# opaq_n1.net
KiCad netlist of a schematic drawn in EAGLE
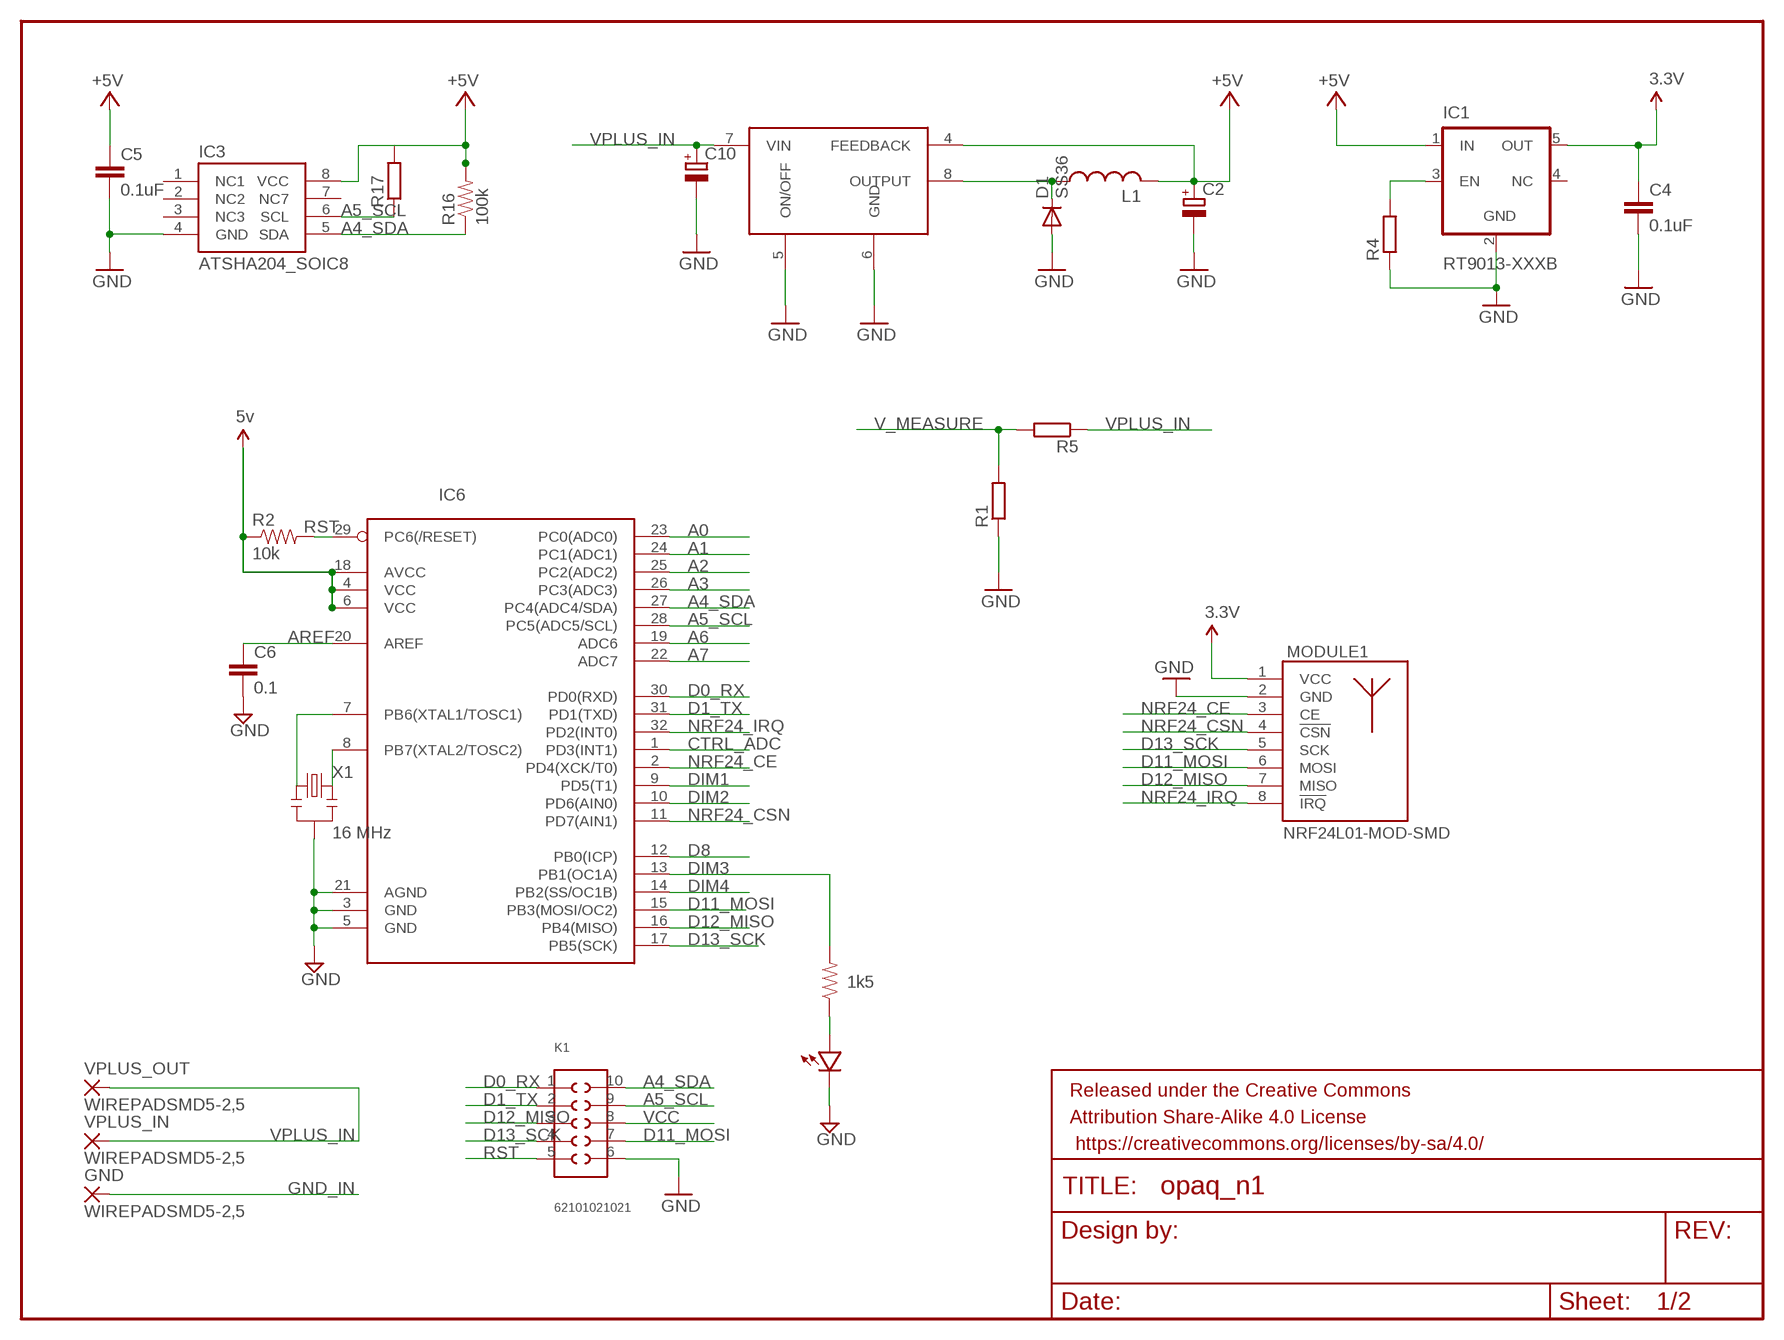
[diagram p0: schematic, sheet 1]
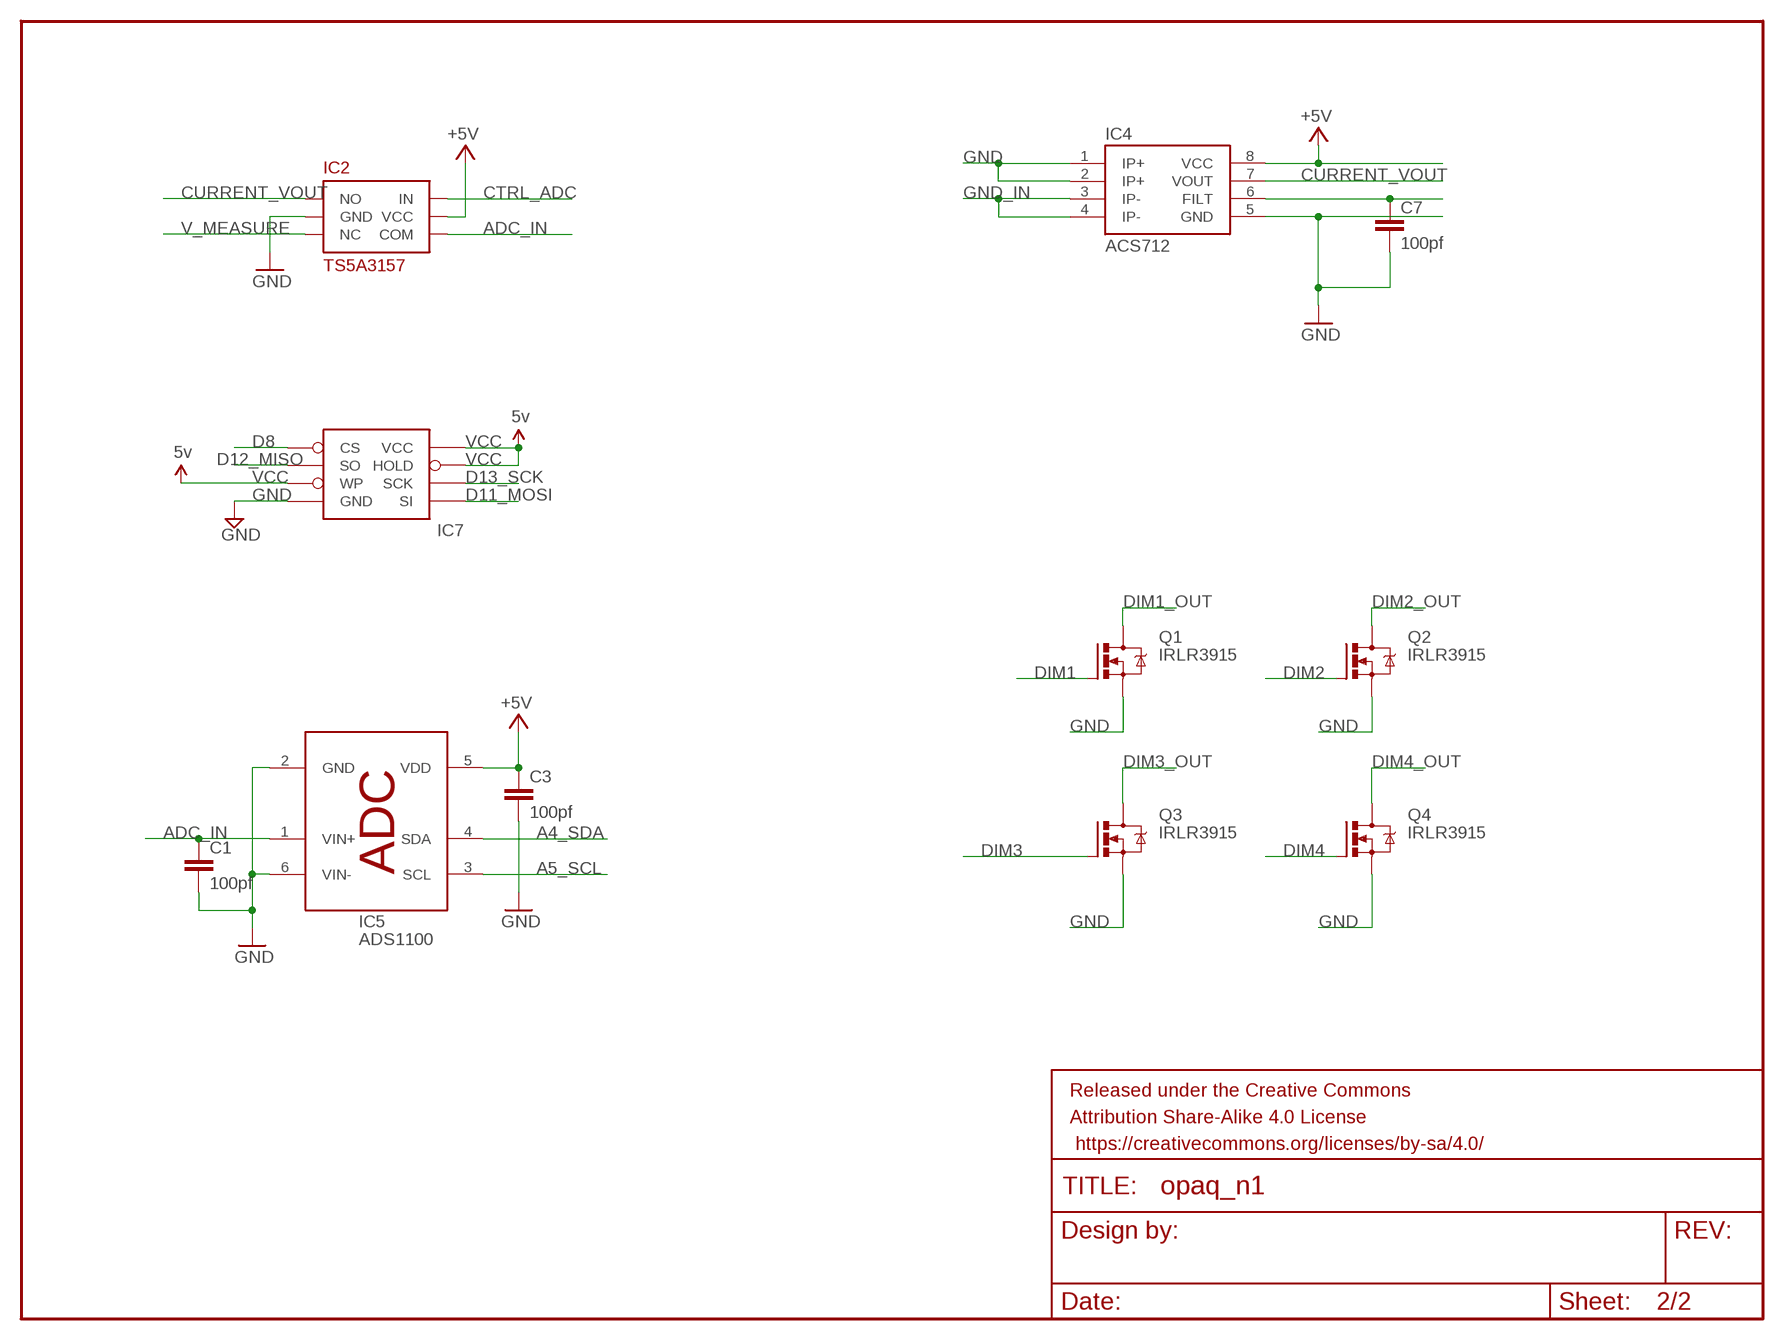
[diagram p1: schematic, sheet 2]

(export (version "E")
  (design (tool "Eeschema 10.0.6"))
  (components
    (comp (ref "C1")
      (value "100pf")
      (footprint "eagle-import:0402-CAP")
      (libsource (lib "eagle-import") (part "SparkFun-Passives_CAP0402-CAP"))
    )
    (comp (ref "C3")
      (value "100pf")
      (footprint "eagle-import:0402-CAP")
      (libsource (lib "eagle-import") (part "SparkFun-Passives_CAP0402-CAP"))
    )
    (comp (ref "C7")
      (value "100pf")
      (footprint "eagle-import:0402-CAP")
      (libsource (lib "eagle-import") (part "SparkFun-Passives_CAP0402-CAP"))
    )
    (comp (ref "FRAME2")
      (value "FRAME-LETTERNO_PACKAGE")
      (footprint "eagle-import:DUMMY")
      (fields (field (name "DESIGNER") "Nobody"))
      (libsource (lib "eagle-import") (part "FRAME-LETTERNO_PACKAGE"))
    )
    (comp (ref "IC2")
      (value "TS5A3157")
      (footprint "eagle-import:SOT23-6")
      (libsource (lib "eagle-import") (part "TS5A3157"))
    )
    (comp (ref "IC4")
      (value "ACS712")
      (footprint "eagle-import:SO08")
      (libsource (lib "eagle-import") (part "ACS712"))
    )
    (comp (ref "IC5")
      (value "ADS1100")
      (footprint "eagle-import:SOT23-6")
      (fields (field (name "MF") "TI"))
      (libsource (lib "eagle-import") (part "ADS1100"))
    )
    (comp (ref "IC7")
      (value "AT25F512BWIDE_5.3MM")
      (footprint "eagle-import:SO08WIDE")
      (libsource (lib "eagle-import") (part "AT25F512BWIDE_5.3MM"))
    )
    (comp (ref "Q1")
      (value "IRLR3915")
      (footprint "eagle-import:D-PAK_TO252AA")
      (libsource (lib "eagle-import") (part "IRLR3915"))
    )
    (comp (ref "Q2")
      (value "IRLR3915")
      (footprint "eagle-import:D-PAK_TO252AA")
      (libsource (lib "eagle-import") (part "IRLR3915"))
    )
    (comp (ref "Q3")
      (value "IRLR3915")
      (footprint "eagle-import:D-PAK_TO252AA")
      (libsource (lib "eagle-import") (part "IRLR3915"))
    )
    (comp (ref "Q4")
      (value "IRLR3915")
      (footprint "eagle-import:D-PAK_TO252AA")
      (libsource (lib "eagle-import") (part "IRLR3915"))
    )
    (comp (ref "C2")
      (value "CPOL-EUC/6032-28R")
      (footprint "eagle-import:C_6032-28R")
      (libsource (lib "eagle-import") (part "CPOL-EUC/6032-28R"))
    )
    (comp (ref "C4")
      (value "0.1uF")
      (footprint "eagle-import:0805")
      (libsource (lib "eagle-import") (part "SparkFun-Passives_CAP0805"))
    )
    (comp (ref "C5")
      (value "0.1uF")
      (footprint "eagle-import:0805")
      (libsource (lib "eagle-import") (part "SparkFun-Passives_CAP0805"))
    )
    (comp (ref "C6")
      (value "0.1")
      (footprint "eagle-import:0603-CAP")
      (libsource (lib "eagle-import") (part "CAP0603-CAP"))
    )
    (comp (ref "C10")
      (value "CPOL-EUD/7343-31R")
      (footprint "eagle-import:D_7343-31R")
      (libsource (lib "eagle-import") (part "CPOL-EUD/7343-31R"))
    )
    (comp (ref "D1")
      (value "SS36")
      (footprint "eagle-import:SMA-DIODE")
      (libsource (lib "eagle-import") (part "DIODESMA"))
    )
    (comp (ref "DIM")
      (value "LED0603")
      (footprint "eagle-import:0603-LED")
      (libsource (lib "eagle-import") (part "LED0603"))
    )
    (comp (ref "FRAME1")
      (value "FRAME-LETTER")
      (footprint "eagle-import:CREATIVE_COMMONS")
      (libsource (lib "eagle-import") (part "FRAME-LETTER"))
    )
    (comp (ref "GND")
      (value "WIREPADSMD5-2,5")
      (footprint "eagle-import:5-2,5")
      (libsource (lib "eagle-import") (part "WIREPADSMD5-2,5"))
    )
    (comp (ref "IC1")
      (value "RT9013-XXXB")
      (footprint "eagle-import:SOT23-5")
      (libsource (lib "eagle-import") (part "RT9013-XXXB"))
    )
    (comp (ref "IC3")
      (value "ATSHA204_SOIC8")
      (footprint "eagle-import:SOIC8")
      (libsource (lib "eagle-import") (part "ATSHA204_SOIC8"))
    )
    (comp (ref "IC6")
      (value "ATMega-328")
      (footprint "eagle-import:MLF32")
      (libsource (lib "eagle-import") (part "ATMEGA168/328MLF"))
    )
    (comp (ref "IC8")
      (value "LM2594HV")
      (footprint "eagle-import:SO08")
      (libsource (lib "eagle-import") (part "LM2594"))
    )
    (comp (ref "K1")
      (value "62101021021")
      (footprint "eagle-import:62101021021")
      (libsource (lib "eagle-import") (part "62101021021"))
    )
    (comp (ref "L1")
      (value "NR6045")
      (footprint "eagle-import:2525")
      (libsource (lib "eagle-import") (part "NR6045"))
    )
    (comp (ref "MODULE1")
      (value "NRF24L01-MOD-SMD")
      (footprint "eagle-import:SMD8-MODULE")
      (libsource (lib "eagle-import") (part "NRF24L01-MOD-SMD"))
    )
    (comp (ref "R1")
      (value "R-EU_R0805")
      (footprint "eagle-import:0805")
      (libsource (lib "eagle-import") (part "R-EU_R0805"))
    )
    (comp (ref "R2")
      (value "10k")
      (footprint "eagle-import:0603-RES")
      (libsource (lib "eagle-import") (part "RESISTOR0603-RES"))
    )
    (comp (ref "R3")
      (value "1k5")
      (footprint "eagle-import:0603-RES")
      (libsource (lib "eagle-import") (part "RESISTOR0603-RES"))
    )
    (comp (ref "R4")
      (value "R-EU_R0805")
      (footprint "eagle-import:0805")
      (libsource (lib "eagle-import") (part "R-EU_R0805"))
    )
    (comp (ref "R5")
      (value "R-EU_R0805")
      (footprint "eagle-import:0805")
      (libsource (lib "eagle-import") (part "R-EU_R0805"))
    )
    (comp (ref "R16")
      (value "100k")
      (footprint "eagle-import:0805")
      (libsource (lib "eagle-import") (part "SparkFun-Passives_RESISTOR0805-RES"))
    )
    (comp (ref "R17")
      (value "R-EU_R0805")
      (footprint "eagle-import:0805")
      (libsource (lib "eagle-import") (part "R-EU_R0805"))
    )
    (comp (ref "VPLUS_IN")
      (value "WIREPADSMD5-2,5")
      (footprint "eagle-import:5-2,5")
      (libsource (lib "eagle-import") (part "WIREPADSMD5-2,5"))
    )
    (comp (ref "VPLUS_OUT")
      (value "WIREPADSMD5-2,5")
      (footprint "eagle-import:5-2,5")
      (libsource (lib "eagle-import") (part "WIREPADSMD5-2,5"))
    )
    (comp (ref "X1")
      (value "16 MHz")
      (footprint "eagle-import:RESONATOR-SMD")
      (libsource (lib "eagle-import") (part "RESONATORSMD"))
    )
  )
  (nets
    (net (code "1") (name "+5V") (class "Default")
      (node (ref "C2") (pin "+") (pinfunction "+_+") (pintype "passive"))
      (node (ref "C3") (pin "1") (pinfunction "1_1") (pintype "passive"))
      (node (ref "C5") (pin "1") (pinfunction "1_1") (pintype "passive"))
      (node (ref "IC1") (pin "1") (pinfunction "IN_1") (pintype "input"))
      (node (ref "IC2") (pin "5") (pinfunction "VCC_5") (pintype "bidirectional"))
      (node (ref "IC3") (pin "8") (pinfunction "VCC_8") (pintype "power_in"))
      (node (ref "IC4") (pin "8") (pinfunction "VCC_8") (pintype "bidirectional"))
      (node (ref "IC5") (pin "5") (pinfunction "VDD_5") (pintype "power_in"))
      (node (ref "IC8") (pin "4") (pinfunction "FEEDBACK_4") (pintype "bidirectional"))
      (node (ref "L1") (pin "P$1") (pinfunction "P$1_P$1") (pintype "passive"))
      (node (ref "R16") (pin "2") (pinfunction "2_2") (pintype "passive"))
      (node (ref "R17") (pin "2") (pinfunction "2_2") (pintype "passive"))
    )
    (net (code "2") (name "3.3V") (class "Default")
      (node (ref "C4") (pin "1") (pinfunction "1_1") (pintype "passive"))
      (node (ref "IC1") (pin "5") (pinfunction "OUT_5") (pintype "passive"))
      (node (ref "MODULE1") (pin "1") (pinfunction "VCC_1") (pintype "power_in"))
    )
    (net (code "3") (name "A0") (class "Default")
      (node (ref "IC6") (pin "23") (pinfunction "PC0(ADC0)_23") (pintype "bidirectional"))
    )
    (net (code "4") (name "A1") (class "Default")
      (node (ref "IC6") (pin "24") (pinfunction "PC1(ADC1)_24") (pintype "bidirectional"))
    )
    (net (code "5") (name "A2") (class "Default")
      (node (ref "IC6") (pin "25") (pinfunction "PC2(ADC2)_25") (pintype "bidirectional"))
    )
    (net (code "6") (name "A3") (class "Default")
      (node (ref "IC6") (pin "26") (pinfunction "PC3(ADC3)_26") (pintype "bidirectional"))
    )
    (net (code "7") (name "A4_SDA") (class "Default")
      (node (ref "IC3") (pin "5") (pinfunction "SDA_5") (pintype "bidirectional"))
      (node (ref "IC5") (pin "4") (pinfunction "SDA_4") (pintype "bidirectional"))
      (node (ref "IC6") (pin "27") (pinfunction "PC4(ADC4/SDA)_27") (pintype "bidirectional"))
      (node (ref "K1") (pin "10") (pinfunction "10_10") (pintype "passive"))
      (node (ref "R16") (pin "1") (pinfunction "1_1") (pintype "passive"))
    )
    (net (code "8") (name "A5_SCL") (class "Default")
      (node (ref "IC3") (pin "6") (pinfunction "SCL_6") (pintype "bidirectional"))
      (node (ref "IC5") (pin "3") (pinfunction "SCL_3") (pintype "input"))
      (node (ref "IC6") (pin "28") (pinfunction "PC5(ADC5/SCL)_28") (pintype "bidirectional"))
      (node (ref "K1") (pin "9") (pinfunction "9_9") (pintype "passive"))
      (node (ref "R17") (pin "1") (pinfunction "1_1") (pintype "passive"))
    )
    (net (code "9") (name "A6") (class "Default")
      (node (ref "IC6") (pin "19") (pinfunction "ADC6_19") (pintype "bidirectional"))
    )
    (net (code "10") (name "A7") (class "Default")
      (node (ref "IC6") (pin "22") (pinfunction "ADC7_22") (pintype "bidirectional"))
    )
    (net (code "11") (name "ADC_IN") (class "Default")
      (node (ref "C1") (pin "1") (pinfunction "1_1") (pintype "passive"))
      (node (ref "IC2") (pin "4") (pinfunction "COM_4") (pintype "bidirectional"))
      (node (ref "IC5") (pin "1") (pinfunction "VIN+_1") (pintype "input"))
    )
    (net (code "12") (name "AREF") (class "Default")
      (node (ref "C6") (pin "1") (pinfunction "1_1") (pintype "passive"))
      (node (ref "IC6") (pin "20") (pinfunction "AREF_20") (pintype "bidirectional"))
    )
    (net (code "13") (name "CTRL_ADC") (class "Default")
      (node (ref "IC2") (pin "6") (pinfunction "IN_6") (pintype "bidirectional"))
      (node (ref "IC6") (pin "1") (pinfunction "PD3(INT1)_1") (pintype "bidirectional"))
    )
    (net (code "14") (name "CURRENT_VOUT") (class "Default")
      (node (ref "IC2") (pin "1") (pinfunction "NO_1") (pintype "bidirectional"))
      (node (ref "IC4") (pin "7") (pinfunction "VOUT_7") (pintype "bidirectional"))
    )
    (net (code "15") (name "D0_RX") (class "Default")
      (node (ref "IC6") (pin "30") (pinfunction "PD0(RXD)_30") (pintype "bidirectional"))
      (node (ref "K1") (pin "1") (pinfunction "1_1") (pintype "passive"))
    )
    (net (code "16") (name "D1_TX") (class "Default")
      (node (ref "IC6") (pin "31") (pinfunction "PD1(TXD)_31") (pintype "bidirectional"))
      (node (ref "K1") (pin "2") (pinfunction "2_2") (pintype "passive"))
    )
    (net (code "17") (name "D8") (class "Default")
      (node (ref "IC6") (pin "12") (pinfunction "PB0(ICP)_12") (pintype "bidirectional"))
      (node (ref "IC7") (pin "1") (pinfunction "CS_1") (pintype "bidirectional"))
    )
    (net (code "18") (name "D11_MOSI") (class "Default")
      (node (ref "IC6") (pin "15") (pinfunction "PB3(MOSI/OC2)_15") (pintype "bidirectional"))
      (node (ref "IC7") (pin "5") (pinfunction "SI_5") (pintype "bidirectional"))
      (node (ref "K1") (pin "7") (pinfunction "7_7") (pintype "passive"))
      (node (ref "MODULE1") (pin "6") (pinfunction "MOSI_6") (pintype "input"))
    )
    (net (code "19") (name "D12_MISO") (class "Default")
      (node (ref "IC6") (pin "16") (pinfunction "PB4(MISO)_16") (pintype "bidirectional"))
      (node (ref "IC7") (pin "2") (pinfunction "SO_2") (pintype "bidirectional"))
      (node (ref "K1") (pin "3") (pinfunction "3_3") (pintype "passive"))
      (node (ref "MODULE1") (pin "7") (pinfunction "MISO_7") (pintype "output"))
    )
    (net (code "20") (name "D13_SCK") (class "Default")
      (node (ref "IC6") (pin "17") (pinfunction "PB5(SCK)_17") (pintype "bidirectional"))
      (node (ref "IC7") (pin "6") (pinfunction "SCK_6") (pintype "bidirectional"))
      (node (ref "K1") (pin "4") (pinfunction "4_4") (pintype "passive"))
      (node (ref "MODULE1") (pin "5") (pinfunction "SCK_5") (pintype "input"))
    )
    (net (code "21") (name "DIM1") (class "Default")
      (node (ref "IC6") (pin "9") (pinfunction "PD5(T1)_9") (pintype "bidirectional"))
      (node (ref "Q1") (pin "1") (pinfunction "G_1") (pintype "passive"))
    )
    (net (code "22") (name "DIM1_OUT") (class "Default")
      (node (ref "Q1") (pin "4") (pinfunction "D_4") (pintype "passive"))
    )
    (net (code "23") (name "DIM2") (class "Default")
      (node (ref "IC6") (pin "10") (pinfunction "PD6(AIN0)_10") (pintype "bidirectional"))
      (node (ref "Q2") (pin "1") (pinfunction "G_1") (pintype "passive"))
    )
    (net (code "24") (name "DIM2_OUT") (class "Default")
      (node (ref "Q2") (pin "4") (pinfunction "D_4") (pintype "passive"))
    )
    (net (code "25") (name "DIM3") (class "Default")
      (node (ref "IC6") (pin "13") (pinfunction "PB1(OC1A)_13") (pintype "bidirectional"))
      (node (ref "Q3") (pin "1") (pinfunction "G_1") (pintype "passive"))
      (node (ref "R3") (pin "2") (pinfunction "2_2") (pintype "passive"))
    )
    (net (code "26") (name "DIM3_OUT") (class "Default")
      (node (ref "Q3") (pin "4") (pinfunction "D_4") (pintype "passive"))
    )
    (net (code "27") (name "DIM4") (class "Default")
      (node (ref "IC6") (pin "14") (pinfunction "PB2(SS/OC1B)_14") (pintype "bidirectional"))
      (node (ref "Q4") (pin "1") (pinfunction "G_1") (pintype "passive"))
    )
    (net (code "28") (name "DIM4_OUT") (class "Default")
      (node (ref "Q4") (pin "4") (pinfunction "D_4") (pintype "passive"))
    )
    (net (code "29") (name "GND") (class "Default")
      (node (ref "C1") (pin "2") (pinfunction "2_2") (pintype "passive"))
      (node (ref "C10") (pin "-") (pinfunction "-_-") (pintype "passive"))
      (node (ref "C2") (pin "-") (pinfunction "-_-") (pintype "passive"))
      (node (ref "C3") (pin "2") (pinfunction "2_2") (pintype "passive"))
      (node (ref "C4") (pin "2") (pinfunction "2_2") (pintype "passive"))
      (node (ref "C5") (pin "2") (pinfunction "2_2") (pintype "passive"))
      (node (ref "C6") (pin "2") (pinfunction "2_2") (pintype "passive"))
      (node (ref "C7") (pin "2") (pinfunction "2_2") (pintype "passive"))
      (node (ref "D1") (pin "A") (pinfunction "A_A") (pintype "passive"))
      (node (ref "DIM") (pin "MINUS") (pinfunction "MINUS_MINUS") (pintype "passive"))
      (node (ref "IC1") (pin "2") (pinfunction "GND_2") (pintype "power_in"))
      (node (ref "IC2") (pin "2") (pinfunction "GND_2") (pintype "bidirectional"))
      (node (ref "IC3") (pin "4") (pinfunction "GND_4") (pintype "power_in"))
      (node (ref "IC4") (pin "1") (pinfunction "IP+_1") (pintype "bidirectional"))
      (node (ref "IC4") (pin "2") (pinfunction "IP+_2") (pintype "bidirectional"))
      (node (ref "IC4") (pin "5") (pinfunction "GND_5") (pintype "bidirectional"))
      (node (ref "IC5") (pin "2") (pinfunction "GND_2") (pintype "power_in"))
      (node (ref "IC5") (pin "6") (pinfunction "VIN-_6") (pintype "input"))
      (node (ref "IC6") (pin "21") (pinfunction "AGND_21") (pintype "bidirectional"))
      (node (ref "IC6") (pin "3") (pinfunction "GND_3") (pintype "bidirectional"))
      (node (ref "IC6") (pin "5") (pinfunction "GND_5") (pintype "bidirectional"))
      (node (ref "IC7") (pin "4") (pinfunction "GND_4") (pintype "bidirectional"))
      (node (ref "IC8") (pin "5") (pinfunction "ON/OFF_5") (pintype "bidirectional"))
      (node (ref "IC8") (pin "6") (pinfunction "GND_6") (pintype "bidirectional"))
      (node (ref "K1") (pin "6") (pinfunction "6_6") (pintype "passive"))
      (node (ref "MODULE1") (pin "2") (pinfunction "GND_2") (pintype "power_in"))
      (node (ref "Q1") (pin "3") (pinfunction "S_3") (pintype "passive"))
      (node (ref "Q2") (pin "3") (pinfunction "S_3") (pintype "passive"))
      (node (ref "Q3") (pin "3") (pinfunction "S_3") (pintype "passive"))
      (node (ref "Q4") (pin "3") (pinfunction "S_3") (pintype "passive"))
      (node (ref "R1") (pin "1") (pinfunction "1_1") (pintype "passive"))
      (node (ref "R4") (pin "1") (pinfunction "1_1") (pintype "passive"))
      (node (ref "X1") (pin "2") (pinfunction "2_2") (pintype "passive"))
    )
    (net (code "30") (name "GND_IN") (class "Default")
      (node (ref "GND") (pin "1") (pinfunction "P_1") (pintype "passive"))
      (node (ref "IC4") (pin "3") (pinfunction "IP-_3") (pintype "bidirectional"))
      (node (ref "IC4") (pin "4") (pinfunction "IP-_4") (pintype "bidirectional"))
    )
    (net (code "31") (name "NRF24_CE") (class "Default")
      (node (ref "IC6") (pin "2") (pinfunction "PD4(XCK/T0)_2") (pintype "bidirectional"))
      (node (ref "MODULE1") (pin "3") (pinfunction "CE_3") (pintype "input"))
    )
    (net (code "32") (name "NRF24_CSN") (class "Default")
      (node (ref "IC6") (pin "11") (pinfunction "PD7(AIN1)_11") (pintype "bidirectional"))
      (node (ref "MODULE1") (pin "4") (pinfunction "~{CSN}_4") (pintype "input"))
    )
    (net (code "33") (name "NRF24_IRQ") (class "Default")
      (node (ref "IC6") (pin "32") (pinfunction "PD2(INT0)_32") (pintype "bidirectional"))
      (node (ref "MODULE1") (pin "8") (pinfunction "~{IRQ}_8") (pintype "open_collector"))
    )
    (net (code "34") (name "Net-(DIM-PadPLUS)") (class "Default")
      (node (ref "DIM") (pin "PLUS") (pinfunction "PLUS_PLUS") (pintype "passive"))
      (node (ref "R3") (pin "1") (pinfunction "1_1") (pintype "passive"))
    )
    (net (code "35") (name "Net-(IC1-EN)") (class "Default")
      (node (ref "IC1") (pin "3") (pinfunction "EN_3") (pintype "input"))
      (node (ref "R4") (pin "2") (pinfunction "2_2") (pintype "passive"))
    )
    (net (code "36") (name "Net-(IC4-FILT)") (class "Default")
      (node (ref "C7") (pin "1") (pinfunction "1_1") (pintype "passive"))
      (node (ref "IC4") (pin "6") (pinfunction "FILT_6") (pintype "bidirectional"))
    )
    (net (code "37") (name "Net-(IC6-PB6(XTAL1{slash}TOSC1))") (class "Default")
      (node (ref "IC6") (pin "7") (pinfunction "PB6(XTAL1/TOSC1)_7") (pintype "bidirectional"))
      (node (ref "X1") (pin "1") (pinfunction "1_1") (pintype "passive"))
    )
    (net (code "38") (name "Net-(IC6-PB7(XTAL2{slash}TOSC2))") (class "Default")
      (node (ref "IC6") (pin "8") (pinfunction "PB7(XTAL2/TOSC2)_8") (pintype "bidirectional"))
      (node (ref "X1") (pin "3") (pinfunction "3_3") (pintype "passive"))
    )
    (net (code "39") (name "Net-(IC8-OUTPUT)") (class "Default")
      (node (ref "D1") (pin "C") (pinfunction "C_C") (pintype "passive"))
      (node (ref "IC8") (pin "8") (pinfunction "OUTPUT_8") (pintype "bidirectional"))
      (node (ref "L1") (pin "P$2") (pinfunction "P$2_P$2") (pintype "passive"))
    )
    (net (code "40") (name "RST") (class "Default")
      (node (ref "IC6") (pin "29") (pinfunction "PC6(/RESET)_29") (pintype "bidirectional"))
      (node (ref "K1") (pin "5") (pinfunction "5_5") (pintype "passive"))
      (node (ref "R2") (pin "2") (pinfunction "2_2") (pintype "passive"))
    )
    (net (code "41") (name "VCC") (class "Default")
      (node (ref "IC6") (pin "18") (pinfunction "AVCC_18") (pintype "bidirectional"))
      (node (ref "IC6") (pin "4") (pinfunction "VCC_4") (pintype "bidirectional"))
      (node (ref "IC6") (pin "6") (pinfunction "VCC_6") (pintype "bidirectional"))
      (node (ref "IC7") (pin "3") (pinfunction "WP_3") (pintype "bidirectional"))
      (node (ref "IC7") (pin "7") (pinfunction "HOLD_7") (pintype "bidirectional"))
      (node (ref "IC7") (pin "8") (pinfunction "VCC_8") (pintype "bidirectional"))
      (node (ref "K1") (pin "8") (pinfunction "8_8") (pintype "passive"))
      (node (ref "R2") (pin "1") (pinfunction "1_1") (pintype "passive"))
    )
    (net (code "42") (name "VPLUS_IN") (class "Default")
      (node (ref "C10") (pin "+") (pinfunction "+_+") (pintype "passive"))
      (node (ref "IC8") (pin "7") (pinfunction "VIN_7") (pintype "bidirectional"))
      (node (ref "R5") (pin "1") (pinfunction "1_1") (pintype "passive"))
      (node (ref "VPLUS_IN") (pin "1") (pinfunction "P_1") (pintype "passive"))
      (node (ref "VPLUS_OUT") (pin "1") (pinfunction "P_1") (pintype "passive"))
    )
    (net (code "43") (name "V_MEASURE") (class "Default")
      (node (ref "IC2") (pin "3") (pinfunction "NC_3") (pintype "bidirectional"))
      (node (ref "R1") (pin "2") (pinfunction "2_2") (pintype "passive"))
      (node (ref "R5") (pin "2") (pinfunction "2_2") (pintype "passive"))
    )
    (net (code "44") (name "unconnected-(IC1-NC-Pad4)") (class "Default")
      (node (ref "IC1") (pin "4") (pinfunction "NC_4") (pintype "no_connect"))
    )
    (net (code "45") (name "unconnected-(IC3-NC1-Pad1)") (class "Default")
      (node (ref "IC3") (pin "1") (pinfunction "NC1_1") (pintype "no_connect"))
    )
    (net (code "46") (name "unconnected-(IC3-NC2-Pad2)") (class "Default")
      (node (ref "IC3") (pin "2") (pinfunction "NC2_2") (pintype "no_connect"))
    )
    (net (code "47") (name "unconnected-(IC3-NC3-Pad3)") (class "Default")
      (node (ref "IC3") (pin "3") (pinfunction "NC3_3") (pintype "no_connect"))
    )
    (net (code "48") (name "unconnected-(IC3-NC7-Pad7)") (class "Default")
      (node (ref "IC3") (pin "7") (pinfunction "NC7_7") (pintype "no_connect"))
    )
  )
)
